# Multiplier.net
KiCad netlist of a schematic drawn in Altium Designer
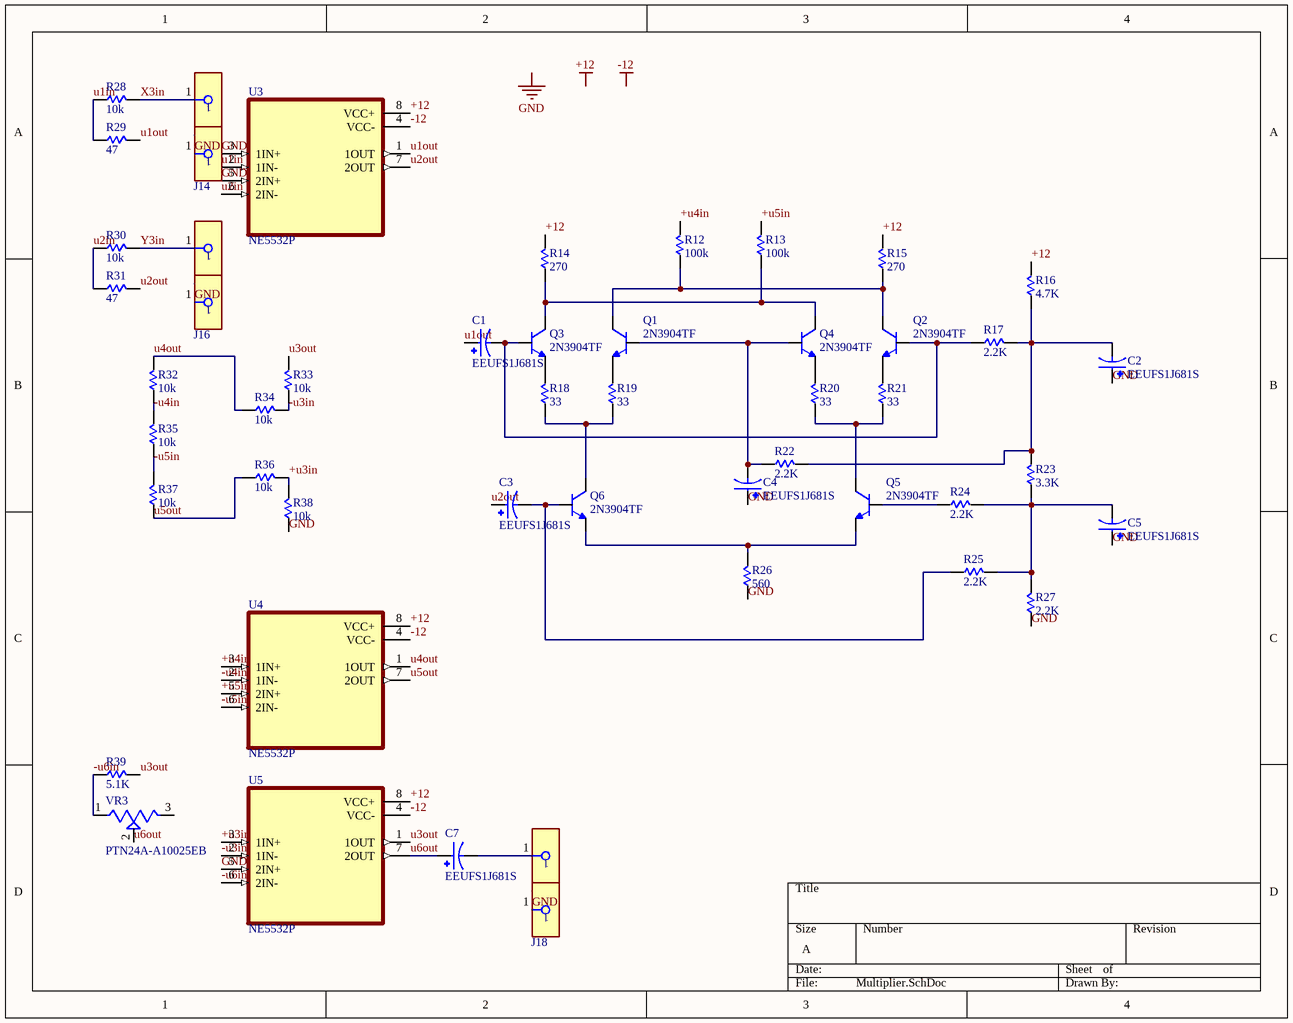
[diagram p0: Multiplier.SchDoc]

(export (version "E")
  (design (tool "Eeschema 10.0.6"))
  (components
    (comp (ref "C1")
      (value "EEUFS1J681S")
      (footprint "CAPPRD250W50D630H1250")
      (description "CAP ALUM 680UF 20% 63V THRU HOLE")
      (fields (field (name "MP") "EEU-FS1J681S") (field (name "MF") "Panasonic Electronic Components"))
      (libsource (lib "") (part "EEUFS1J681S_1"))
    )
    (comp (ref "C2")
      (value "EEUFS1J681S")
      (footprint "CAPPRD250W50D630H1250")
      (description "CAP ALUM 680UF 20% 63V THRU HOLE")
      (fields (field (name "MP") "EEU-FS1J681S") (field (name "MF") "Panasonic Electronic Components"))
      (libsource (lib "Schlib1") (part "EEUFS1J681S"))
    )
    (comp (ref "C3")
      (value "EEUFS1J681S")
      (footprint "CAPPRD250W50D630H1250")
      (description "CAP ALUM 680UF 20% 63V THRU HOLE")
      (fields (field (name "MP") "EEU-FS1J681S") (field (name "MF") "Panasonic Electronic Components"))
      (libsource (lib "") (part "EEUFS1J681S_1"))
    )
    (comp (ref "C4")
      (value "EEUFS1J681S")
      (footprint "CAPPRD250W50D630H1250")
      (description "CAP ALUM 680UF 20% 63V THRU HOLE")
      (fields (field (name "MP") "EEU-FS1J681S") (field (name "MF") "Panasonic Electronic Components"))
      (libsource (lib "Schlib1") (part "EEUFS1J681S"))
    )
    (comp (ref "C5")
      (value "EEUFS1J681S")
      (footprint "CAPPRD250W50D630H1250")
      (description "CAP ALUM 680UF 20% 63V THRU HOLE")
      (fields (field (name "MP") "EEU-FS1J681S") (field (name "MF") "Panasonic Electronic Components"))
      (libsource (lib "Schlib1") (part "EEUFS1J681S"))
    )
    (comp (ref "C7")
      (value "EEUFS1J681S")
      (footprint "CAPPRD250W50D630H1250")
      (description "CAP ALUM 680UF 20% 63V THRU HOLE")
      (fields (field (name "MP") "EEU-FS1J681S") (field (name "MF") "Panasonic Electronic Components"))
      (libsource (lib "") (part "EEUFS1J681S_1"))
    )
    (comp (ref "J13")
      (value "1581-5")
      (footprint "FP-1581-5-MFG")
      (description "CONN BANANA JACK TURRET GREEN")
      (libsource (lib "Schlib1") (part "CMP-73906-000011-1"))
    )
    (comp (ref "J14")
      (value "1581-5")
      (footprint "FP-1581-5-MFG")
      (description "CONN BANANA JACK TURRET GREEN")
      (libsource (lib "Schlib1") (part "CMP-73906-000011-1"))
    )
    (comp (ref "J15")
      (value "1581-5")
      (footprint "FP-1581-5-MFG")
      (description "CONN BANANA JACK TURRET GREEN")
      (libsource (lib "Schlib1") (part "CMP-73906-000011-1"))
    )
    (comp (ref "J16")
      (value "1581-5")
      (footprint "FP-1581-5-MFG")
      (description "CONN BANANA JACK TURRET GREEN")
      (libsource (lib "Schlib1") (part "CMP-73906-000011-1"))
    )
    (comp (ref "J17")
      (value "1581-5")
      (footprint "FP-1581-5-MFG")
      (description "CONN BANANA JACK TURRET GREEN")
      (libsource (lib "Schlib1") (part "CMP-73906-000011-1"))
    )
    (comp (ref "J18")
      (value "1581-5")
      (footprint "FP-1581-5-MFG")
      (description "CONN BANANA JACK TURRET GREEN")
      (libsource (lib "Schlib1") (part "CMP-73906-000011-1"))
    )
    (comp (ref "Q1")
      (value "2N3904TF")
      (footprint "TO92254P520H877-3")
      (description "Transistor General Purpose BJT NPN 40 Volt 0.2 Amp 3-Pin TO-92 Tape And Reel")
      (fields (field (name "MF") "Fairchild Semiconductor"))
      (libsource (lib "Schlib1") (part "2N3904TF"))
    )
    (comp (ref "Q2")
      (value "2N3904TF")
      (footprint "TO92254P520H877-3")
      (description "Transistor General Purpose BJT NPN 40 Volt 0.2 Amp 3-Pin TO-92 Tape And Reel")
      (fields (field (name "MF") "Fairchild Semiconductor"))
      (libsource (lib "Schlib1") (part "2N3904TF"))
    )
    (comp (ref "Q3")
      (value "2N3904TF")
      (footprint "TO92254P520H877-3")
      (description "Transistor General Purpose BJT NPN 40 Volt 0.2 Amp 3-Pin TO-92 Tape And Reel")
      (fields (field (name "MF") "Fairchild Semiconductor"))
      (libsource (lib "Schlib1") (part "2N3904TF"))
    )
    (comp (ref "Q4")
      (value "2N3904TF")
      (footprint "TO92254P520H877-3")
      (description "Transistor General Purpose BJT NPN 40 Volt 0.2 Amp 3-Pin TO-92 Tape And Reel")
      (fields (field (name "MF") "Fairchild Semiconductor"))
      (libsource (lib "Schlib1") (part "2N3904TF"))
    )
    (comp (ref "Q5")
      (value "2N3904TF")
      (footprint "TO92254P520H877-3")
      (description "Transistor General Purpose BJT NPN 40 Volt 0.2 Amp 3-Pin TO-92 Tape And Reel")
      (fields (field (name "MF") "Fairchild Semiconductor"))
      (libsource (lib "Schlib1") (part "2N3904TF"))
    )
    (comp (ref "Q6")
      (value "2N3904TF")
      (footprint "TO92254P520H877-3")
      (description "Transistor General Purpose BJT NPN 40 Volt 0.2 Amp 3-Pin TO-92 Tape And Reel")
      (fields (field (name "MF") "Fairchild Semiconductor"))
      (libsource (lib "Schlib1") (part "2N3904TF"))
    )
    (comp (ref "R12")
      (value "100k")
      (footprint "RESAD1100W55L680D260")
      (description "1.07 kOhms Â±1% 0.25W, 1/4W Through Hole Resistor Axial - Metal Film")
      (fields (field (name "MF") "Yageo") (field (name "MP") "MFR-25FBF52-1K"))
      (libsource (lib "Schlib1") (part "MFR-25FBF52-1K"))
    )
    (comp (ref "R13")
      (value "100k")
      (footprint "RESAD1100W55L680D260")
      (description "1.07 kOhms Â±1% 0.25W, 1/4W Through Hole Resistor Axial - Metal Film")
      (fields (field (name "MF") "Yageo") (field (name "MP") "MFR-25FBF52-1K"))
      (libsource (lib "Schlib1") (part "MFR-25FBF52-1K"))
    )
    (comp (ref "R14")
      (value "270")
      (footprint "RESAD1100W55L680D260")
      (description "1.07 kOhms Â±1% 0.25W, 1/4W Through Hole Resistor Axial - Metal Film")
      (fields (field (name "MF") "Yageo") (field (name "MP") "MFR-25FBF52-1K"))
      (libsource (lib "Schlib1") (part "MFR-25FBF52-1K"))
    )
    (comp (ref "R15")
      (value "270")
      (footprint "RESAD1100W55L680D260")
      (description "1.07 kOhms Â±1% 0.25W, 1/4W Through Hole Resistor Axial - Metal Film")
      (fields (field (name "MF") "Yageo") (field (name "MP") "MFR-25FBF52-1K"))
      (libsource (lib "Schlib1") (part "MFR-25FBF52-1K"))
    )
    (comp (ref "R16")
      (value "4.7K")
      (footprint "RESAD1100W55L680D260")
      (description "1.07 kOhms Â±1% 0.25W, 1/4W Through Hole Resistor Axial - Metal Film")
      (fields (field (name "MF") "Yageo") (field (name "MP") "MFR-25FBF52-1K"))
      (libsource (lib "Schlib1") (part "MFR-25FBF52-1K"))
    )
    (comp (ref "R17")
      (value "2.2K")
      (footprint "RESAD1100W55L680D260")
      (description "1.07 kOhms Â±1% 0.25W, 1/4W Through Hole Resistor Axial - Metal Film")
      (fields (field (name "MF") "Yageo") (field (name "MP") "MFR-25FBF52-1K"))
      (libsource (lib "Schlib1") (part "MFR-25FBF52-1K"))
    )
    (comp (ref "R18")
      (value "33")
      (footprint "RESAD1100W55L680D260")
      (description "1.07 kOhms Â±1% 0.25W, 1/4W Through Hole Resistor Axial - Metal Film")
      (fields (field (name "MF") "Yageo") (field (name "MP") "MFR-25FBF52-1K"))
      (libsource (lib "Schlib1") (part "MFR-25FBF52-1K"))
    )
    (comp (ref "R19")
      (value "33")
      (footprint "RESAD1100W55L680D260")
      (description "1.07 kOhms Â±1% 0.25W, 1/4W Through Hole Resistor Axial - Metal Film")
      (fields (field (name "MF") "Yageo") (field (name "MP") "MFR-25FBF52-1K"))
      (libsource (lib "Schlib1") (part "MFR-25FBF52-1K"))
    )
    (comp (ref "R20")
      (value "33")
      (footprint "RESAD1100W55L680D260")
      (description "1.07 kOhms Â±1% 0.25W, 1/4W Through Hole Resistor Axial - Metal Film")
      (fields (field (name "MF") "Yageo") (field (name "MP") "MFR-25FBF52-1K"))
      (libsource (lib "Schlib1") (part "MFR-25FBF52-1K"))
    )
    (comp (ref "R21")
      (value "33")
      (footprint "RESAD1100W55L680D260")
      (description "1.07 kOhms Â±1% 0.25W, 1/4W Through Hole Resistor Axial - Metal Film")
      (fields (field (name "MF") "Yageo") (field (name "MP") "MFR-25FBF52-1K"))
      (libsource (lib "Schlib1") (part "MFR-25FBF52-1K"))
    )
    (comp (ref "R22")
      (value "2.2K")
      (footprint "RESAD1100W55L680D260")
      (description "1.07 kOhms Â±1% 0.25W, 1/4W Through Hole Resistor Axial - Metal Film")
      (fields (field (name "MF") "Yageo") (field (name "MP") "MFR-25FBF52-1K"))
      (libsource (lib "Schlib1") (part "MFR-25FBF52-1K"))
    )
    (comp (ref "R23")
      (value "3.3K")
      (footprint "RESAD1100W55L680D260")
      (description "1.07 kOhms Â±1% 0.25W, 1/4W Through Hole Resistor Axial - Metal Film")
      (fields (field (name "MF") "Yageo") (field (name "MP") "MFR-25FBF52-1K"))
      (libsource (lib "Schlib1") (part "MFR-25FBF52-1K"))
    )
    (comp (ref "R24")
      (value "2.2K")
      (footprint "RESAD1100W55L680D260")
      (description "1.07 kOhms Â±1% 0.25W, 1/4W Through Hole Resistor Axial - Metal Film")
      (fields (field (name "MF") "Yageo") (field (name "MP") "MFR-25FBF52-1K"))
      (libsource (lib "Schlib1") (part "MFR-25FBF52-1K"))
    )
    (comp (ref "R25")
      (value "2.2K")
      (footprint "RESAD1100W55L680D260")
      (description "1.07 kOhms Â±1% 0.25W, 1/4W Through Hole Resistor Axial - Metal Film")
      (fields (field (name "MF") "Yageo") (field (name "MP") "MFR-25FBF52-1K"))
      (libsource (lib "Schlib1") (part "MFR-25FBF52-1K"))
    )
    (comp (ref "R26")
      (value "560")
      (footprint "RESAD1100W55L680D260")
      (description "1.07 kOhms Â±1% 0.25W, 1/4W Through Hole Resistor Axial - Metal Film")
      (fields (field (name "MF") "Yageo") (field (name "MP") "MFR-25FBF52-1K"))
      (libsource (lib "Schlib1") (part "MFR-25FBF52-1K"))
    )
    (comp (ref "R27")
      (value "2.2K")
      (footprint "RESAD1100W55L680D260")
      (description "1.07 kOhms Â±1% 0.25W, 1/4W Through Hole Resistor Axial - Metal Film")
      (fields (field (name "MF") "Yageo") (field (name "MP") "MFR-25FBF52-1K"))
      (libsource (lib "Schlib1") (part "MFR-25FBF52-1K"))
    )
    (comp (ref "R28")
      (value "10k")
      (footprint "RESAD1100W55L680D260")
      (description "1.07 kOhms Â±1% 0.25W, 1/4W Through Hole Resistor Axial - Metal Film")
      (fields (field (name "MF") "Yageo") (field (name "MP") "MFR-25FBF52-1K"))
      (libsource (lib "Schlib1") (part "MFR-25FBF52-1K"))
    )
    (comp (ref "R29")
      (value "47")
      (footprint "RESAD1100W55L680D260")
      (description "1.07 kOhms Â±1% 0.25W, 1/4W Through Hole Resistor Axial - Metal Film")
      (fields (field (name "MF") "Yageo") (field (name "MP") "MFR-25FBF52-1K"))
      (libsource (lib "Schlib1") (part "MFR-25FBF52-1K"))
    )
    (comp (ref "R30")
      (value "10k")
      (footprint "RESAD1100W55L680D260")
      (description "1.07 kOhms Â±1% 0.25W, 1/4W Through Hole Resistor Axial - Metal Film")
      (fields (field (name "MF") "Yageo") (field (name "MP") "MFR-25FBF52-1K"))
      (libsource (lib "Schlib1") (part "MFR-25FBF52-1K"))
    )
    (comp (ref "R31")
      (value "47")
      (footprint "RESAD1100W55L680D260")
      (description "1.07 kOhms Â±1% 0.25W, 1/4W Through Hole Resistor Axial - Metal Film")
      (fields (field (name "MF") "Yageo") (field (name "MP") "MFR-25FBF52-1K"))
      (libsource (lib "Schlib1") (part "MFR-25FBF52-1K"))
    )
    (comp (ref "R32")
      (value "10k")
      (footprint "RESAD1100W55L680D260")
      (description "1.07 kOhms Â±1% 0.25W, 1/4W Through Hole Resistor Axial - Metal Film")
      (fields (field (name "MF") "Yageo") (field (name "MP") "MFR-25FBF52-1K"))
      (libsource (lib "Schlib1") (part "MFR-25FBF52-1K"))
    )
    (comp (ref "R33")
      (value "10k")
      (footprint "RESAD1100W55L680D260")
      (description "1.07 kOhms Â±1% 0.25W, 1/4W Through Hole Resistor Axial - Metal Film")
      (fields (field (name "MF") "Yageo") (field (name "MP") "MFR-25FBF52-1K"))
      (libsource (lib "Schlib1") (part "MFR-25FBF52-1K"))
    )
    (comp (ref "R34")
      (value "10k")
      (footprint "RESAD1100W55L680D260")
      (description "1.07 kOhms Â±1% 0.25W, 1/4W Through Hole Resistor Axial - Metal Film")
      (fields (field (name "MF") "Yageo") (field (name "MP") "MFR-25FBF52-1K"))
      (libsource (lib "Schlib1") (part "MFR-25FBF52-1K"))
    )
    (comp (ref "R35")
      (value "10k")
      (footprint "RESAD1100W55L680D260")
      (description "1.07 kOhms Â±1% 0.25W, 1/4W Through Hole Resistor Axial - Metal Film")
      (fields (field (name "MF") "Yageo") (field (name "MP") "MFR-25FBF52-1K"))
      (libsource (lib "Schlib1") (part "MFR-25FBF52-1K"))
    )
    (comp (ref "R36")
      (value "10k")
      (footprint "RESAD1100W55L680D260")
      (description "1.07 kOhms Â±1% 0.25W, 1/4W Through Hole Resistor Axial - Metal Film")
      (fields (field (name "MF") "Yageo") (field (name "MP") "MFR-25FBF52-1K"))
      (libsource (lib "Schlib1") (part "MFR-25FBF52-1K"))
    )
    (comp (ref "R37")
      (value "10k")
      (footprint "RESAD1100W55L680D260")
      (description "1.07 kOhms Â±1% 0.25W, 1/4W Through Hole Resistor Axial - Metal Film")
      (fields (field (name "MF") "Yageo") (field (name "MP") "MFR-25FBF52-1K"))
      (libsource (lib "Schlib1") (part "MFR-25FBF52-1K"))
    )
    (comp (ref "R38")
      (value "10k")
      (footprint "RESAD1100W55L680D260")
      (description "1.07 kOhms Â±1% 0.25W, 1/4W Through Hole Resistor Axial - Metal Film")
      (fields (field (name "MF") "Yageo") (field (name "MP") "MFR-25FBF52-1K"))
      (libsource (lib "Schlib1") (part "MFR-25FBF52-1K"))
    )
    (comp (ref "R39")
      (value "5.1K")
      (footprint "RESAD1100W55L680D260")
      (description "1.07 kOhms Â±1% 0.25W, 1/4W Through Hole Resistor Axial - Metal Film")
      (fields (field (name "MF") "Yageo") (field (name "MP") "MFR-25FBF52-1K"))
      (libsource (lib "Schlib1") (part "MFR-25FBF52-1K"))
    )
    (comp (ref "U3")
      (value "NE5532P")
      (footprint "DIP794W45P254L959H508Q8")
      (description "Dual, 30-V, 10-MHz, low-noise operational amplifier for audio applications")
      (fields (field (name "MF") "Texas Instruments"))
      (libsource (lib "Schlib1") (part "NE5532P"))
    )
    (comp (ref "U4")
      (value "NE5532P")
      (footprint "DIP794W45P254L959H508Q8")
      (description "Dual, 30-V, 10-MHz, low-noise operational amplifier for audio applications")
      (fields (field (name "MF") "Texas Instruments"))
      (libsource (lib "Schlib1") (part "NE5532P"))
    )
    (comp (ref "U5")
      (value "NE5532P")
      (footprint "DIP794W45P254L959H508Q8")
      (description "Dual, 30-V, 10-MHz, low-noise operational amplifier for audio applications")
      (fields (field (name "MF") "Texas Instruments"))
      (libsource (lib "Schlib1") (part "NE5532P"))
    )
    (comp (ref "VR3")
      (value "PTN24A-A10025EB")
      (footprint "TRIM_PTN24A-A10025EB")
      (description "100k Ohm 1 Gang Linear Panel Mount Potentiometer 1.0 Turns Carbon 0.5W, 1/2W PC Pins")
      (fields (field (name "MF") "Same Sky"))
      (libsource (lib "Schlib1") (part "PTN24A-A10025EB"))
    )
  )
  (nets
    (net (code "1") (name "+12") (class "Default")
      (node (ref "R14") (pin "2") (pinfunction "2_2") (pintype "passive"))
      (node (ref "R15") (pin "2") (pinfunction "2_2") (pintype "passive"))
      (node (ref "R16") (pin "2") (pinfunction "2_2") (pintype "passive"))
      (node (ref "U3") (pin "8") (pinfunction "VCC+_8") (pintype "power_in"))
      (node (ref "U4") (pin "8") (pinfunction "VCC+_8") (pintype "power_in"))
      (node (ref "U5") (pin "8") (pinfunction "VCC+_8") (pintype "power_in"))
    )
    (net (code "2") (name "-12") (class "Default")
      (node (ref "U3") (pin "4") (pinfunction "VCC-_4") (pintype "power_in"))
      (node (ref "U4") (pin "4") (pinfunction "VCC-_4") (pintype "power_in"))
      (node (ref "U5") (pin "4") (pinfunction "VCC-_4") (pintype "power_in"))
    )
    (net (code "3") (name "/+u3in") (class "Default")
      (node (ref "R36") (pin "2") (pinfunction "2_2") (pintype "passive"))
      (node (ref "R38") (pin "2") (pinfunction "2_2") (pintype "passive"))
      (node (ref "U5") (pin "3") (pinfunction "1IN+_3") (pintype "input"))
    )
    (net (code "4") (name "/+u4in") (class "Default")
      (node (ref "R12") (pin "2") (pinfunction "2_2") (pintype "passive"))
      (node (ref "U4") (pin "3") (pinfunction "1IN+_3") (pintype "input"))
    )
    (net (code "5") (name "/+u5in") (class "Default")
      (node (ref "R13") (pin "2") (pinfunction "2_2") (pintype "passive"))
      (node (ref "U4") (pin "5") (pinfunction "2IN+_5") (pintype "input"))
    )
    (net (code "6") (name "/-u3in") (class "Default")
      (node (ref "R33") (pin "1") (pinfunction "1_1") (pintype "passive"))
      (node (ref "R34") (pin "2") (pinfunction "2_2") (pintype "passive"))
      (node (ref "U5") (pin "2") (pinfunction "1IN-_2") (pintype "input"))
    )
    (net (code "7") (name "/-u4in") (class "Default")
      (node (ref "R32") (pin "1") (pinfunction "1_1") (pintype "passive"))
      (node (ref "R35") (pin "2") (pinfunction "2_2") (pintype "passive"))
      (node (ref "U4") (pin "2") (pinfunction "1IN-_2") (pintype "input"))
    )
    (net (code "8") (name "/-u5in") (class "Default")
      (node (ref "R35") (pin "1") (pinfunction "1_1") (pintype "passive"))
      (node (ref "R37") (pin "2") (pinfunction "2_2") (pintype "passive"))
      (node (ref "U4") (pin "6") (pinfunction "2IN-_6") (pintype "input"))
    )
    (net (code "9") (name "/-u6in") (class "Default")
      (node (ref "R39") (pin "1") (pinfunction "1_1") (pintype "passive"))
      (node (ref "U5") (pin "6") (pinfunction "2IN-_6") (pintype "input"))
      (node (ref "VR3") (pin "1") (pinfunction "1_1") (pintype "passive"))
    )
    (net (code "10") (name "/X3in") (class "Default")
      (node (ref "J13") (pin "1") (pinfunction "1_1") (pintype "passive"))
      (node (ref "R28") (pin "2") (pinfunction "2_2") (pintype "passive"))
    )
    (net (code "11") (name "/Y3in") (class "Default")
      (node (ref "J15") (pin "1") (pinfunction "1_1") (pintype "passive"))
      (node (ref "R30") (pin "2") (pinfunction "2_2") (pintype "passive"))
    )
    (net (code "12") (name "/u1in") (class "Default")
      (node (ref "R28") (pin "1") (pinfunction "1_1") (pintype "passive"))
      (node (ref "R29") (pin "1") (pinfunction "1_1") (pintype "passive"))
      (node (ref "U3") (pin "2") (pinfunction "1IN-_2") (pintype "input"))
    )
    (net (code "13") (name "/u1out") (class "Default")
      (node (ref "C1") (pin "P") (pinfunction "P_P") (pintype "passive"))
      (node (ref "R29") (pin "2") (pinfunction "2_2") (pintype "passive"))
      (node (ref "U3") (pin "1") (pinfunction "1OUT_1") (pintype "output"))
    )
    (net (code "14") (name "/u2in") (class "Default")
      (node (ref "R30") (pin "1") (pinfunction "1_1") (pintype "passive"))
      (node (ref "R31") (pin "1") (pinfunction "1_1") (pintype "passive"))
      (node (ref "U3") (pin "6") (pinfunction "2IN-_6") (pintype "input"))
    )
    (net (code "15") (name "/u2out") (class "Default")
      (node (ref "C3") (pin "P") (pinfunction "P_P") (pintype "passive"))
      (node (ref "R31") (pin "2") (pinfunction "2_2") (pintype "passive"))
      (node (ref "U3") (pin "7") (pinfunction "2OUT_7") (pintype "output"))
    )
    (net (code "16") (name "/u3out") (class "Default")
      (node (ref "R33") (pin "2") (pinfunction "2_2") (pintype "passive"))
      (node (ref "R39") (pin "2") (pinfunction "2_2") (pintype "passive"))
      (node (ref "U5") (pin "1") (pinfunction "1OUT_1") (pintype "output"))
    )
    (net (code "17") (name "/u4out") (class "Default")
      (node (ref "R32") (pin "2") (pinfunction "2_2") (pintype "passive"))
      (node (ref "R34") (pin "1") (pinfunction "1_1") (pintype "passive"))
      (node (ref "U4") (pin "1") (pinfunction "1OUT_1") (pintype "output"))
    )
    (net (code "18") (name "/u5out") (class "Default")
      (node (ref "R36") (pin "1") (pinfunction "1_1") (pintype "passive"))
      (node (ref "R37") (pin "1") (pinfunction "1_1") (pintype "passive"))
      (node (ref "U4") (pin "7") (pinfunction "2OUT_7") (pintype "output"))
    )
    (net (code "19") (name "/u6out") (class "Default")
      (node (ref "C7") (pin "P") (pinfunction "P_P") (pintype "passive"))
      (node (ref "U5") (pin "7") (pinfunction "2OUT_7") (pintype "output"))
      (node (ref "VR3") (pin "2") (pinfunction "2_2") (pintype "passive"))
    )
    (net (code "20") (name "GND") (class "Default")
      (node (ref "C2") (pin "P") (pinfunction "P_P") (pintype "passive"))
      (node (ref "C4") (pin "P") (pinfunction "P_P") (pintype "passive"))
      (node (ref "C5") (pin "P") (pinfunction "P_P") (pintype "passive"))
      (node (ref "J14") (pin "1") (pinfunction "1_1") (pintype "passive"))
      (node (ref "J16") (pin "1") (pinfunction "1_1") (pintype "passive"))
      (node (ref "J18") (pin "1") (pinfunction "1_1") (pintype "passive"))
      (node (ref "R26") (pin "1") (pinfunction "1_1") (pintype "passive"))
      (node (ref "R27") (pin "1") (pinfunction "1_1") (pintype "passive"))
      (node (ref "R38") (pin "1") (pinfunction "1_1") (pintype "passive"))
      (node (ref "U3") (pin "3") (pinfunction "1IN+_3") (pintype "input"))
      (node (ref "U3") (pin "5") (pinfunction "2IN+_5") (pintype "input"))
      (node (ref "U5") (pin "5") (pinfunction "2IN+_5") (pintype "input"))
    )
    (net (code "21") (name "Net-(C2-PadN)") (class "Default")
      (node (ref "C2") (pin "N") (pinfunction "N_N") (pintype "passive"))
      (node (ref "R16") (pin "1") (pinfunction "1_1") (pintype "passive"))
      (node (ref "R17") (pin "2") (pinfunction "2_2") (pintype "passive"))
      (node (ref "R22") (pin "2") (pinfunction "2_2") (pintype "passive"))
      (node (ref "R23") (pin "2") (pinfunction "2_2") (pintype "passive"))
    )
    (net (code "22") (name "Net-(C5-PadN)") (class "Default")
      (node (ref "C5") (pin "N") (pinfunction "N_N") (pintype "passive"))
      (node (ref "R23") (pin "1") (pinfunction "1_1") (pintype "passive"))
      (node (ref "R24") (pin "2") (pinfunction "2_2") (pintype "passive"))
      (node (ref "R25") (pin "2") (pinfunction "2_2") (pintype "passive"))
      (node (ref "R27") (pin "2") (pinfunction "2_2") (pintype "passive"))
    )
    (net (code "23") (name "Net-(C7-PadN)") (class "Default")
      (node (ref "C7") (pin "N") (pinfunction "N_N") (pintype "passive"))
      (node (ref "J17") (pin "1") (pinfunction "1_1") (pintype "passive"))
    )
    (net (code "24") (name "Net-(Q1-B)") (class "Default")
      (node (ref "C4") (pin "N") (pinfunction "N_N") (pintype "passive"))
      (node (ref "Q1") (pin "2") (pinfunction "B_2") (pintype "passive"))
      (node (ref "Q4") (pin "2") (pinfunction "B_2") (pintype "passive"))
      (node (ref "R22") (pin "1") (pinfunction "1_1") (pintype "passive"))
    )
    (net (code "25") (name "Net-(Q1-C)") (class "Default")
      (node (ref "Q1") (pin "3") (pinfunction "C_3") (pintype "passive"))
      (node (ref "Q2") (pin "3") (pinfunction "C_3") (pintype "passive"))
      (node (ref "R12") (pin "1") (pinfunction "1_1") (pintype "passive"))
      (node (ref "R15") (pin "1") (pinfunction "1_1") (pintype "passive"))
    )
    (net (code "26") (name "Net-(Q1-E)") (class "Default")
      (node (ref "Q1") (pin "1") (pinfunction "E_1") (pintype "passive"))
      (node (ref "R19") (pin "2") (pinfunction "2_2") (pintype "passive"))
    )
    (net (code "27") (name "Net-(Q2-B)") (class "Default")
      (node (ref "C1") (pin "N") (pinfunction "N_N") (pintype "passive"))
      (node (ref "Q2") (pin "2") (pinfunction "B_2") (pintype "passive"))
      (node (ref "Q3") (pin "2") (pinfunction "B_2") (pintype "passive"))
      (node (ref "R17") (pin "1") (pinfunction "1_1") (pintype "passive"))
    )
    (net (code "28") (name "Net-(Q2-E)") (class "Default")
      (node (ref "Q2") (pin "1") (pinfunction "E_1") (pintype "passive"))
      (node (ref "R21") (pin "2") (pinfunction "2_2") (pintype "passive"))
    )
    (net (code "29") (name "Net-(Q3-C)") (class "Default")
      (node (ref "Q3") (pin "3") (pinfunction "C_3") (pintype "passive"))
      (node (ref "Q4") (pin "3") (pinfunction "C_3") (pintype "passive"))
      (node (ref "R13") (pin "1") (pinfunction "1_1") (pintype "passive"))
      (node (ref "R14") (pin "1") (pinfunction "1_1") (pintype "passive"))
    )
    (net (code "30") (name "Net-(Q3-E)") (class "Default")
      (node (ref "Q3") (pin "1") (pinfunction "E_1") (pintype "passive"))
      (node (ref "R18") (pin "2") (pinfunction "2_2") (pintype "passive"))
    )
    (net (code "31") (name "Net-(Q4-E)") (class "Default")
      (node (ref "Q4") (pin "1") (pinfunction "E_1") (pintype "passive"))
      (node (ref "R20") (pin "2") (pinfunction "2_2") (pintype "passive"))
    )
    (net (code "32") (name "Net-(Q5-B)") (class "Default")
      (node (ref "Q5") (pin "2") (pinfunction "B_2") (pintype "passive"))
      (node (ref "R24") (pin "1") (pinfunction "1_1") (pintype "passive"))
    )
    (net (code "33") (name "Net-(Q5-C)") (class "Default")
      (node (ref "Q5") (pin "3") (pinfunction "C_3") (pintype "passive"))
      (node (ref "R20") (pin "1") (pinfunction "1_1") (pintype "passive"))
      (node (ref "R21") (pin "1") (pinfunction "1_1") (pintype "passive"))
    )
    (net (code "34") (name "Net-(Q5-E)") (class "Default")
      (node (ref "Q5") (pin "1") (pinfunction "E_1") (pintype "passive"))
      (node (ref "Q6") (pin "1") (pinfunction "E_1") (pintype "passive"))
      (node (ref "R26") (pin "2") (pinfunction "2_2") (pintype "passive"))
    )
    (net (code "35") (name "Net-(Q6-B)") (class "Default")
      (node (ref "C3") (pin "N") (pinfunction "N_N") (pintype "passive"))
      (node (ref "Q6") (pin "2") (pinfunction "B_2") (pintype "passive"))
      (node (ref "R25") (pin "1") (pinfunction "1_1") (pintype "passive"))
    )
    (net (code "36") (name "Net-(Q6-C)") (class "Default")
      (node (ref "Q6") (pin "3") (pinfunction "C_3") (pintype "passive"))
      (node (ref "R18") (pin "1") (pinfunction "1_1") (pintype "passive"))
      (node (ref "R19") (pin "1") (pinfunction "1_1") (pintype "passive"))
    )
    (net (code "37") (name "unconnected-(VR3-Pad3)") (class "Default")
      (node (ref "VR3") (pin "3") (pinfunction "3_3") (pintype "passive"))
    )
  )
)
